# Atmega32_test.net
KiCad netlist of a schematic drawn in EAGLE
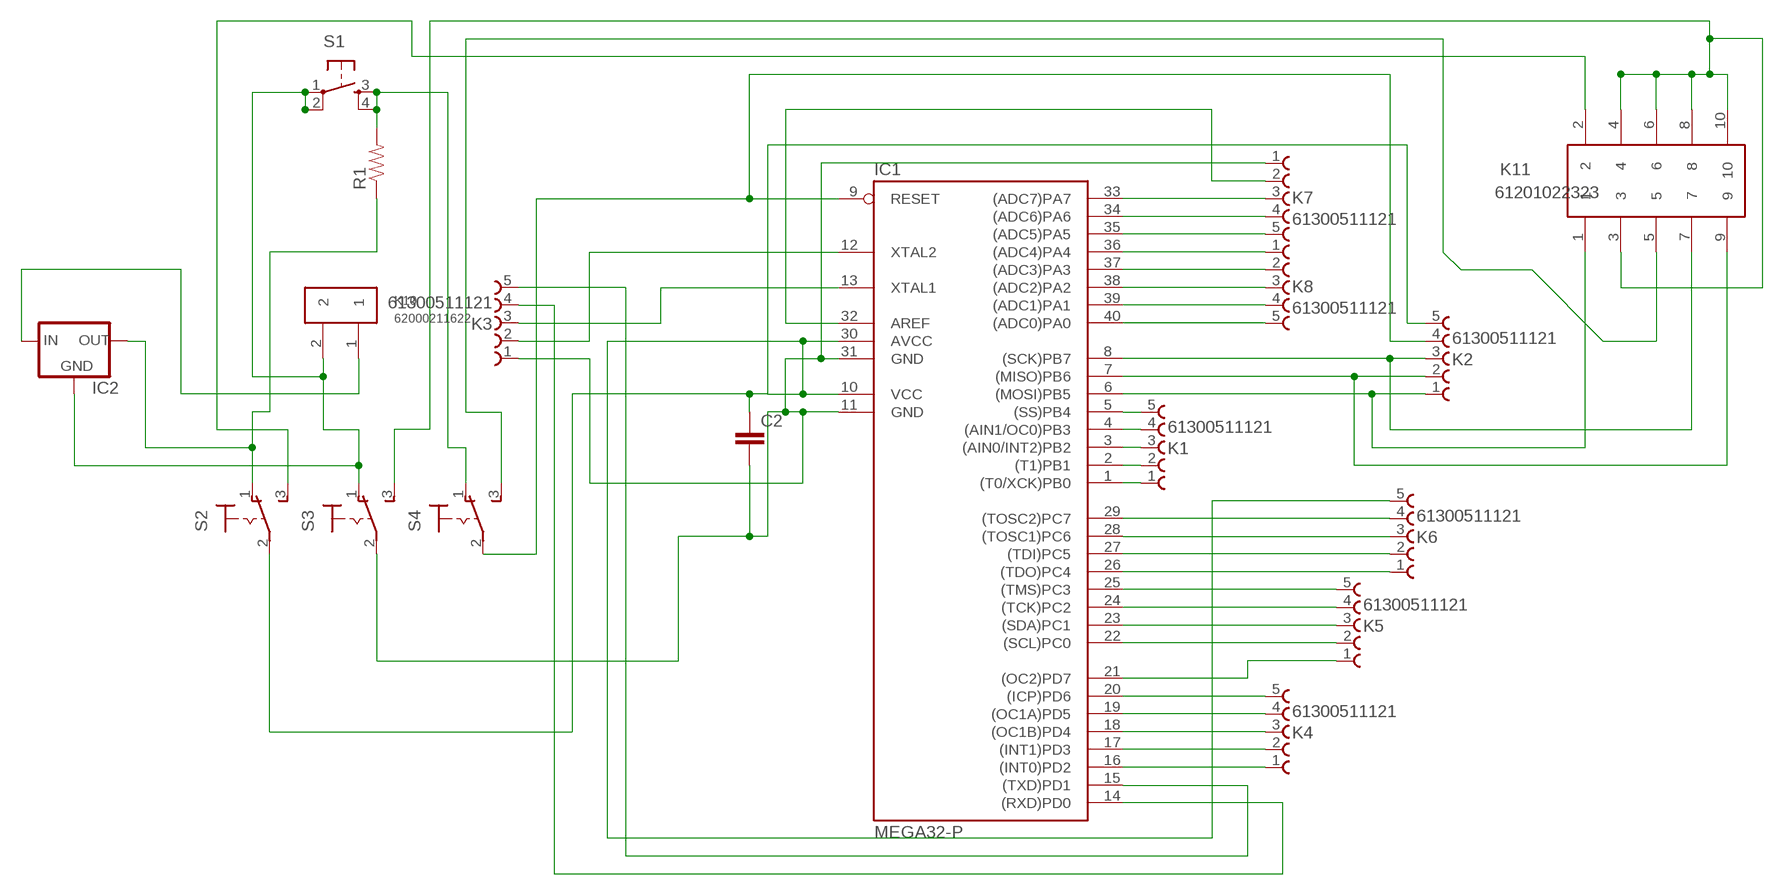
[diagram p0: schematic, sheet 1]

(export (version "E")
  (design (tool "Eeschema 10.0.6"))
  (components
    (comp (ref "C2")
      (value "C10/6")
      (footprint "eagle-import:C10B6")
      (libsource (lib "eagle-import") (part "C10/6"))
    )
    (comp (ref "IC1")
      (value "MEGA32-P")
      (footprint "eagle-import:DIL40")
      (fields (field (name "MPN") "ATMEGA32-16PU"))
      (libsource (lib "eagle-import") (part "MEGA32-P"))
    )
    (comp (ref "IC2")
      (value "V_REG_78XX-TO-220")
      (footprint "eagle-import:TO-220-ALT")
      (libsource (lib "eagle-import") (part "V_REG_78XX-TO-220"))
    )
    (comp (ref "K1")
      (value "61300511121")
      (footprint "eagle-import:61300511121")
      (libsource (lib "eagle-import") (part "61300511121"))
    )
    (comp (ref "K2")
      (value "61300511121")
      (footprint "eagle-import:61300511121")
      (libsource (lib "eagle-import") (part "61300511121"))
    )
    (comp (ref "K3")
      (value "61300511121")
      (footprint "eagle-import:61300511121")
      (libsource (lib "eagle-import") (part "61300511121"))
    )
    (comp (ref "K4")
      (value "61300511121")
      (footprint "eagle-import:61300511121")
      (libsource (lib "eagle-import") (part "61300511121"))
    )
    (comp (ref "K5")
      (value "61300511121")
      (footprint "eagle-import:61300511121")
      (libsource (lib "eagle-import") (part "61300511121"))
    )
    (comp (ref "K6")
      (value "61300511121")
      (footprint "eagle-import:61300511121")
      (libsource (lib "eagle-import") (part "61300511121"))
    )
    (comp (ref "K7")
      (value "61300511121")
      (footprint "eagle-import:61300511121")
      (libsource (lib "eagle-import") (part "61300511121"))
    )
    (comp (ref "K8")
      (value "61300511121")
      (footprint "eagle-import:61300511121")
      (libsource (lib "eagle-import") (part "61300511121"))
    )
    (comp (ref "K10")
      (value "62000211622")
      (footprint "eagle-import:62000211622")
      (libsource (lib "eagle-import") (part "62000211622"))
    )
    (comp (ref "K11")
      (value "61201022323")
      (footprint "eagle-import:61201022323")
      (libsource (lib "eagle-import") (part "61201022323"))
    )
    (comp (ref "R1")
      (value "10KOHM1/6W5%(PTH)KIT")
      (footprint "eagle-import:AXIAL-0.3-KIT")
      (libsource (lib "eagle-import") (part "10KOHM1/6W5%(PTH)KIT"))
    )
    (comp (ref "S1")
      (value "TAC_SWITCHPTH")
      (footprint "eagle-import:TACTILE-PTH")
      (libsource (lib "eagle-import") (part "TAC_SWITCHPTH"))
    )
    (comp (ref "S2")
      (value "320-916")
      (footprint "eagle-import:320-916")
      (libsource (lib "eagle-import") (part "320-916"))
    )
    (comp (ref "S3")
      (value "320-916")
      (footprint "eagle-import:320-916")
      (libsource (lib "eagle-import") (part "320-916"))
    )
    (comp (ref "S4")
      (value "320-916")
      (footprint "eagle-import:320-916")
      (libsource (lib "eagle-import") (part "320-916"))
    )
  )
  (nets
    (net (code "1") (name "Net-(IC1-(ADC0)PA0)") (class "Default")
      (node (ref "IC1") (pin "40") (pinfunction "(ADC0)PA0_40") (pintype "bidirectional"))
      (node (ref "K8") (pin "5") (pinfunction "5_5") (pintype "passive"))
    )
    (net (code "2") (name "Net-(IC1-(ADC1)PA1)") (class "Default")
      (node (ref "IC1") (pin "39") (pinfunction "(ADC1)PA1_39") (pintype "bidirectional"))
      (node (ref "K8") (pin "4") (pinfunction "4_4") (pintype "passive"))
    )
    (net (code "3") (name "Net-(IC1-(ADC2)PA2)") (class "Default")
      (node (ref "IC1") (pin "38") (pinfunction "(ADC2)PA2_38") (pintype "bidirectional"))
      (node (ref "K8") (pin "3") (pinfunction "3_3") (pintype "passive"))
    )
    (net (code "4") (name "Net-(IC1-(ADC3)PA3)") (class "Default")
      (node (ref "IC1") (pin "37") (pinfunction "(ADC3)PA3_37") (pintype "bidirectional"))
      (node (ref "K8") (pin "2") (pinfunction "2_2") (pintype "passive"))
    )
    (net (code "5") (name "Net-(IC1-(ADC4)PA4)") (class "Default")
      (node (ref "IC1") (pin "36") (pinfunction "(ADC4)PA4_36") (pintype "bidirectional"))
      (node (ref "K8") (pin "1") (pinfunction "1_1") (pintype "passive"))
    )
    (net (code "6") (name "Net-(IC1-(ADC5)PA5)") (class "Default")
      (node (ref "IC1") (pin "35") (pinfunction "(ADC5)PA5_35") (pintype "bidirectional"))
      (node (ref "K7") (pin "5") (pinfunction "5_5") (pintype "passive"))
    )
    (net (code "7") (name "Net-(IC1-(ADC6)PA6)") (class "Default")
      (node (ref "IC1") (pin "34") (pinfunction "(ADC6)PA6_34") (pintype "bidirectional"))
      (node (ref "K7") (pin "4") (pinfunction "4_4") (pintype "passive"))
    )
    (net (code "8") (name "Net-(IC1-(ADC7)PA7)") (class "Default")
      (node (ref "IC1") (pin "33") (pinfunction "(ADC7)PA7_33") (pintype "bidirectional"))
      (node (ref "K7") (pin "3") (pinfunction "3_3") (pintype "passive"))
    )
    (net (code "9") (name "Net-(IC1-(AIN0{slash}INT2)PB2)") (class "Default")
      (node (ref "IC1") (pin "3") (pinfunction "(AIN0/INT2)PB2_3") (pintype "bidirectional"))
      (node (ref "K1") (pin "3") (pinfunction "3_3") (pintype "passive"))
    )
    (net (code "10") (name "Net-(IC1-(AIN1{slash}OC0)PB3)") (class "Default")
      (node (ref "IC1") (pin "4") (pinfunction "(AIN1/OC0)PB3_4") (pintype "bidirectional"))
      (node (ref "K1") (pin "4") (pinfunction "4_4") (pintype "passive"))
    )
    (net (code "11") (name "Net-(IC1-(ICP)PD6)") (class "Default")
      (node (ref "IC1") (pin "20") (pinfunction "(ICP)PD6_20") (pintype "bidirectional"))
      (node (ref "K4") (pin "5") (pinfunction "5_5") (pintype "passive"))
    )
    (net (code "12") (name "Net-(IC1-(INT0)PD2)") (class "Default")
      (node (ref "IC1") (pin "16") (pinfunction "(INT0)PD2_16") (pintype "bidirectional"))
      (node (ref "K4") (pin "1") (pinfunction "1_1") (pintype "passive"))
    )
    (net (code "13") (name "Net-(IC1-(INT1)PD3)") (class "Default")
      (node (ref "IC1") (pin "17") (pinfunction "(INT1)PD3_17") (pintype "bidirectional"))
      (node (ref "K4") (pin "2") (pinfunction "2_2") (pintype "passive"))
    )
    (net (code "14") (name "Net-(IC1-(MISO)PB6)") (class "Default")
      (node (ref "IC1") (pin "7") (pinfunction "(MISO)PB6_7") (pintype "bidirectional"))
      (node (ref "K11") (pin "9") (pinfunction "9_9") (pintype "passive"))
      (node (ref "K2") (pin "2") (pinfunction "2_2") (pintype "passive"))
    )
    (net (code "15") (name "Net-(IC1-(MOSI)PB5)") (class "Default")
      (node (ref "IC1") (pin "6") (pinfunction "(MOSI)PB5_6") (pintype "bidirectional"))
      (node (ref "K11") (pin "1") (pinfunction "1_1") (pintype "passive"))
      (node (ref "K2") (pin "1") (pinfunction "1_1") (pintype "passive"))
    )
    (net (code "16") (name "Net-(IC1-(OC1A)PD5)") (class "Default")
      (node (ref "IC1") (pin "19") (pinfunction "(OC1A)PD5_19") (pintype "bidirectional"))
      (node (ref "K4") (pin "4") (pinfunction "4_4") (pintype "passive"))
    )
    (net (code "17") (name "Net-(IC1-(OC1B)PD4)") (class "Default")
      (node (ref "IC1") (pin "18") (pinfunction "(OC1B)PD4_18") (pintype "bidirectional"))
      (node (ref "K4") (pin "3") (pinfunction "3_3") (pintype "passive"))
    )
    (net (code "18") (name "Net-(IC1-(OC2)PD7)") (class "Default")
      (node (ref "IC1") (pin "21") (pinfunction "(OC2)PD7_21") (pintype "bidirectional"))
      (node (ref "K5") (pin "1") (pinfunction "1_1") (pintype "passive"))
    )
    (net (code "19") (name "Net-(IC1-(RXD)PD0)") (class "Default")
      (node (ref "IC1") (pin "14") (pinfunction "(RXD)PD0_14") (pintype "bidirectional"))
      (node (ref "K3") (pin "4") (pinfunction "4_4") (pintype "passive"))
    )
    (net (code "20") (name "Net-(IC1-(SCK)PB7)") (class "Default")
      (node (ref "IC1") (pin "8") (pinfunction "(SCK)PB7_8") (pintype "bidirectional"))
      (node (ref "K11") (pin "7") (pinfunction "7_7") (pintype "passive"))
      (node (ref "K2") (pin "3") (pinfunction "3_3") (pintype "passive"))
    )
    (net (code "21") (name "Net-(IC1-(SCL)PC0)") (class "Default")
      (node (ref "IC1") (pin "22") (pinfunction "(SCL)PC0_22") (pintype "bidirectional"))
      (node (ref "K5") (pin "2") (pinfunction "2_2") (pintype "passive"))
    )
    (net (code "22") (name "Net-(IC1-(SDA)PC1)") (class "Default")
      (node (ref "IC1") (pin "23") (pinfunction "(SDA)PC1_23") (pintype "bidirectional"))
      (node (ref "K5") (pin "3") (pinfunction "3_3") (pintype "passive"))
    )
    (net (code "23") (name "Net-(IC1-(SS)PB4)") (class "Default")
      (node (ref "IC1") (pin "5") (pinfunction "(SS)PB4_5") (pintype "bidirectional"))
      (node (ref "K1") (pin "5") (pinfunction "5_5") (pintype "passive"))
    )
    (net (code "24") (name "Net-(IC1-(T0{slash}XCK)PB0)") (class "Default")
      (node (ref "IC1") (pin "1") (pinfunction "(T0/XCK)PB0_1") (pintype "bidirectional"))
      (node (ref "K1") (pin "1") (pinfunction "1_1") (pintype "passive"))
    )
    (net (code "25") (name "Net-(IC1-(T1)PB1)") (class "Default")
      (node (ref "IC1") (pin "2") (pinfunction "(T1)PB1_2") (pintype "bidirectional"))
      (node (ref "K1") (pin "2") (pinfunction "2_2") (pintype "passive"))
    )
    (net (code "26") (name "Net-(IC1-(TCK)PC2)") (class "Default")
      (node (ref "IC1") (pin "24") (pinfunction "(TCK)PC2_24") (pintype "bidirectional"))
      (node (ref "K5") (pin "4") (pinfunction "4_4") (pintype "passive"))
    )
    (net (code "27") (name "Net-(IC1-(TDI)PC5)") (class "Default")
      (node (ref "IC1") (pin "27") (pinfunction "(TDI)PC5_27") (pintype "bidirectional"))
      (node (ref "K6") (pin "2") (pinfunction "2_2") (pintype "passive"))
    )
    (net (code "28") (name "Net-(IC1-(TDO)PC4)") (class "Default")
      (node (ref "IC1") (pin "26") (pinfunction "(TDO)PC4_26") (pintype "bidirectional"))
      (node (ref "K6") (pin "1") (pinfunction "1_1") (pintype "passive"))
    )
    (net (code "29") (name "Net-(IC1-(TMS)PC3)") (class "Default")
      (node (ref "IC1") (pin "25") (pinfunction "(TMS)PC3_25") (pintype "bidirectional"))
      (node (ref "K5") (pin "5") (pinfunction "5_5") (pintype "passive"))
    )
    (net (code "30") (name "Net-(IC1-(TOSC1)PC6)") (class "Default")
      (node (ref "IC1") (pin "28") (pinfunction "(TOSC1)PC6_28") (pintype "bidirectional"))
      (node (ref "K6") (pin "3") (pinfunction "3_3") (pintype "passive"))
    )
    (net (code "31") (name "Net-(IC1-(TOSC2)PC7)") (class "Default")
      (node (ref "IC1") (pin "29") (pinfunction "(TOSC2)PC7_29") (pintype "bidirectional"))
      (node (ref "K6") (pin "4") (pinfunction "4_4") (pintype "passive"))
    )
    (net (code "32") (name "Net-(IC1-(TXD)PD1)") (class "Default")
      (node (ref "IC1") (pin "15") (pinfunction "(TXD)PD1_15") (pintype "bidirectional"))
      (node (ref "K3") (pin "5") (pinfunction "5_5") (pintype "passive"))
    )
    (net (code "33") (name "Net-(IC1-AREF)") (class "Default")
      (node (ref "IC1") (pin "32") (pinfunction "AREF_32") (pintype "passive"))
      (node (ref "K7") (pin "2") (pinfunction "2_2") (pintype "passive"))
    )
    (net (code "34") (name "Net-(IC1-AVCC)") (class "Default")
      (node (ref "C2") (pin "1") (pinfunction "1_1") (pintype "passive"))
      (node (ref "IC1") (pin "10") (pinfunction "VCC_10") (pintype "power_in"))
      (node (ref "IC1") (pin "30") (pinfunction "AVCC_30") (pintype "power_in"))
      (node (ref "K2") (pin "5") (pinfunction "5_5") (pintype "passive"))
      (node (ref "K6") (pin "5") (pinfunction "5_5") (pintype "passive"))
      (node (ref "S2") (pin "2") (pinfunction "P_2") (pintype "passive"))
    )
    (net (code "35") (name "Net-(IC1-RESET)") (class "Default")
      (node (ref "IC1") (pin "9") (pinfunction "RESET_9") (pintype "input"))
      (node (ref "K2") (pin "4") (pinfunction "4_4") (pintype "passive"))
      (node (ref "S4") (pin "2") (pinfunction "P_2") (pintype "passive"))
    )
    (net (code "36") (name "Net-(IC1-XTAL1)") (class "Default")
      (node (ref "IC1") (pin "13") (pinfunction "XTAL1_13") (pintype "bidirectional"))
      (node (ref "K3") (pin "3") (pinfunction "3_3") (pintype "passive"))
    )
    (net (code "37") (name "Net-(IC1-XTAL2)") (class "Default")
      (node (ref "IC1") (pin "12") (pinfunction "XTAL2_12") (pintype "bidirectional"))
      (node (ref "K3") (pin "2") (pinfunction "2_2") (pintype "passive"))
    )
    (net (code "38") (name "Net-(IC2-PadIN)") (class "Default")
      (node (ref "IC2") (pin "IN") (pinfunction "IN_IN") (pintype "input"))
      (node (ref "K10") (pin "1") (pinfunction "1_1") (pintype "bidirectional"))
    )
    (net (code "39") (name "Net-(R1-1)") (class "Default")
      (node (ref "IC2") (pin "OUT") (pinfunction "OUT_OUT") (pintype "output"))
      (node (ref "R1") (pin "P$1") (pinfunction "1_P$1") (pintype "passive"))
      (node (ref "S2") (pin "1") (pinfunction "O_1") (pintype "passive"))
    )
    (net (code "40") (name "Net-(R1-2)") (class "Default")
      (node (ref "R1") (pin "P$2") (pinfunction "2_P$2") (pintype "passive"))
      (node (ref "S1") (pin "3") (pinfunction "3_3") (pintype "passive"))
      (node (ref "S1") (pin "4") (pinfunction "4_4") (pintype "passive"))
      (node (ref "S4") (pin "1") (pinfunction "O_1") (pintype "passive"))
    )
    (net (code "41") (name "Net-(S2-S)") (class "Default")
      (node (ref "K11") (pin "2") (pinfunction "2_2") (pintype "passive"))
      (node (ref "S2") (pin "3") (pinfunction "S_3") (pintype "passive"))
    )
    (net (code "42") (name "Net-(S3-O)") (class "Default")
      (node (ref "IC2") (pin "GND") (pinfunction "GND_GND") (pintype "input"))
      (node (ref "K10") (pin "2") (pinfunction "2_2") (pintype "bidirectional"))
      (node (ref "S1") (pin "1") (pinfunction "1_1") (pintype "passive"))
      (node (ref "S1") (pin "2") (pinfunction "2_2") (pintype "passive"))
      (node (ref "S3") (pin "1") (pinfunction "O_1") (pintype "passive"))
    )
    (net (code "43") (name "Net-(S3-P)") (class "Default")
      (node (ref "C2") (pin "2") (pinfunction "2_2") (pintype "passive"))
      (node (ref "IC1") (pin "11") (pinfunction "GND_11") (pintype "power_in"))
      (node (ref "IC1") (pin "31") (pinfunction "GND_31") (pintype "power_in"))
      (node (ref "K3") (pin "1") (pinfunction "1_1") (pintype "passive"))
      (node (ref "K7") (pin "1") (pinfunction "1_1") (pintype "passive"))
      (node (ref "S3") (pin "2") (pinfunction "P_2") (pintype "passive"))
    )
    (net (code "44") (name "Net-(S3-S)") (class "Default")
      (node (ref "K11") (pin "10") (pinfunction "10_10") (pintype "passive"))
      (node (ref "K11") (pin "3") (pinfunction "3_3") (pintype "passive"))
      (node (ref "K11") (pin "4") (pinfunction "4_4") (pintype "passive"))
      (node (ref "K11") (pin "6") (pinfunction "6_6") (pintype "passive"))
      (node (ref "K11") (pin "8") (pinfunction "8_8") (pintype "passive"))
      (node (ref "S3") (pin "3") (pinfunction "S_3") (pintype "passive"))
    )
    (net (code "45") (name "Net-(S4-S)") (class "Default")
      (node (ref "K11") (pin "5") (pinfunction "5_5") (pintype "passive"))
      (node (ref "S4") (pin "3") (pinfunction "S_3") (pintype "passive"))
    )
  )
)
